# Pulser.net
KiCad netlist of a schematic drawn in Altium Designer
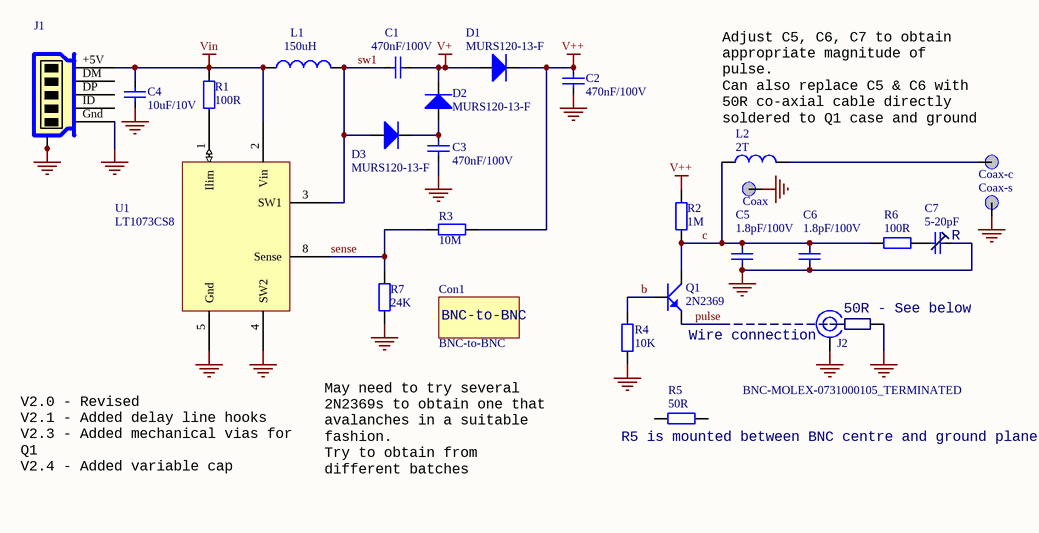
[diagram p0: Pulser.SchDoc]

(export (version "E")
  (design (tool "Eeschema 10.0.6"))
  (components
    (comp (ref "C1")
      (value "470nF/100V")
      (footprint "CCNP3216-1206")
      (description "Capacitor")
      (fields
        (field (name "MANUFACTURER") "Generic Components")
        (field (name "PUBLISHER") "Altium Hobart Technology Centre")
      )
      (libsource (lib "MyLibrary") (part "Cap"))
    )
    (comp (ref "C2")
      (value "470nF/100V")
      (footprint "CCNP3216-1206")
      (description "Capacitor")
      (fields
        (field (name "MANUFACTURER") "Generic Components")
        (field (name "PUBLISHER") "Altium Hobart Technology Centre")
      )
      (libsource (lib "MyLibrary") (part "Cap"))
    )
    (comp (ref "C3")
      (value "470nF/100V")
      (footprint "CCNP3216-1206")
      (description "Capacitor")
      (fields
        (field (name "MANUFACTURER") "Generic Components")
        (field (name "PUBLISHER") "Altium Hobart Technology Centre")
      )
      (libsource (lib "MyLibrary") (part "Cap"))
    )
    (comp (ref "C4")
      (value "10uF/10V")
      (footprint "CCNP2012-0805")
      (description "Capacitor SMT 0805")
      (fields
        (field (name "MANUFACTURER") "Generic Components")
        (field (name "PUBLISHER") "Altium Hobart Technology Centre")
      )
      (libsource (lib "MyLibrary") (part "Cap_CCNP_0805"))
    )
    (comp (ref "C5")
      (value "1.8pF/100V")
      (footprint "CCNP2012-0805")
      (description "Capacitor")
      (fields
        (field (name "MANUFACTURER") "Generic Components")
        (field (name "PUBLISHER") "Altium Hobart Technology Centre")
      )
      (libsource (lib "MyLibrary") (part "Cap"))
    )
    (comp (ref "C6")
      (value "1.8pF/100V")
      (footprint "CCNP2012-0805")
      (description "Capacitor")
      (fields
        (field (name "MANUFACTURER") "Generic Components")
        (field (name "PUBLISHER") "Altium Hobart Technology Centre")
      )
      (libsource (lib "MyLibrary") (part "Cap"))
    )
    (comp (ref "C7")
      (value "5-20pF")
      (footprint "MyPcbLib:CAP_TRIM_SMT_TZC3")
      (description "Trimmer Capacitor muRata TZC3 series")
      (fields
        (field (name "MANUFACTURER") "Generic Components")
        (field (name "PUBLISHER") "Altium Hobart Technology Centre")
      )
      (libsource (lib "MySchLib") (part "Cap_Trimmer_TZC3"))
    )
    (comp (ref "Coax") (value "PAD") (footprint "Pad") (libsource (lib "MyLibrary") (part "PAD")))
    (comp (ref "Coax-c") (value "PAD") (footprint "Pad") (libsource (lib "MyLibrary") (part "PAD")))
    (comp (ref "Coax-s") (value "PAD") (footprint "Pad") (libsource (lib "MyLibrary") (part "PAD")))
    (comp (ref "Con1")
      (value "BNC-to-BNC")
      (footprint "BNC-to-BNC")
      (libsource (lib "MySchLib") (part "BNC-to-BNC"))
    )
    (comp (ref "D1")
      (value "MURS120-13-F")
      (footprint "SMB_Diode")
      (description "Fast / Ultrafast Diode, 200 V, 1 A")
      (fields
        (field (name "MANUFACTURER") "Generic Components")
        (field (name "PUBLISHER") "Altium Hobart Technology Centre")
      )
      (libsource (lib "MySchLib") (part "MURS120-13-F"))
    )
    (comp (ref "D2")
      (value "MURS120-13-F")
      (footprint "SMB_Diode")
      (description "Fast / Ultrafast Diode, 200 V, 1 A")
      (fields
        (field (name "MANUFACTURER") "Generic Components")
        (field (name "PUBLISHER") "Altium Hobart Technology Centre")
      )
      (libsource (lib "MySchLib") (part "MURS120-13-F"))
    )
    (comp (ref "D3")
      (value "MURS120-13-F")
      (footprint "SMB_Diode")
      (description "Fast / Ultrafast Diode, 200 V, 1 A")
      (fields
        (field (name "MANUFACTURER") "Generic Components")
        (field (name "PUBLISHER") "Altium Hobart Technology Centre")
      )
      (libsource (lib "MySchLib") (part "MURS120-13-F"))
    )
    (comp (ref "J1")
      (value "USB_MICRO_B_CONNECTOR")
      (footprint "MOLEX - 47346-0001")
      (description "USB Micro-B Connector")
      (libsource (lib "MyLibrary") (part "USB_MICRO_B_CONNECTOR"))
    )
    (comp (ref "J2")
      (value "BNC-MOLEX-0731000105_TERMINATED")
      (footprint "BNC_RA CON - Molex - Resistor")
      (description "BNC Connector")
      (libsource (lib "MyLibrary") (part "BNC-MOLEX-0731000105_TERMINATED"))
    )
    (comp (ref "L1")
      (value "150uH")
      (footprint "INDUCTOR_SMT")
      (description "Inductor - SMT 3mm")
      (libsource (lib "MySchLib") (part "INDUCTOR-SMT"))
    )
    (comp (ref "L2")
      (value "2T")
      (footprint "CL2012-0805")
      (description "Resistor")
      (fields
        (field (name "MANUFACTURER") "Generic Components")
        (field (name "PUBLISHER") "Altium Hobart Technology Centre")
      )
      (libsource (lib "MyLibrary") (part "Ind_CL0805"))
    )
    (comp (ref "Q1")
      (value "2N2369")
      (footprint "TO-18-flush")
      (description "High Speed Switching Transistor")
      (libsource (lib "MySchLib") (part "2N2369"))
    )
    (comp (ref "R1")
      (value "100R")
      (footprint "CR2012-0805")
      (description "Resistor")
      (fields
        (field (name "MANUFACTURER") "Generic Components")
        (field (name "PUBLISHER") "Altium Hobart Technology Centre")
      )
      (libsource (lib "") (part "Res_1"))
    )
    (comp (ref "R2")
      (value "1M")
      (footprint "CR2012-0805")
      (description "Resistor")
      (fields
        (field (name "MANUFACTURER") "Generic Components")
        (field (name "PUBLISHER") "Altium Hobart Technology Centre")
      )
      (libsource (lib "") (part "Res_1"))
    )
    (comp (ref "R3")
      (value "10M")
      (footprint "CR2012-0805")
      (description "Resistor")
      (fields
        (field (name "MANUFACTURER") "Generic Components")
        (field (name "PUBLISHER") "Altium Hobart Technology Centre")
      )
      (libsource (lib "") (part "Res_2"))
    )
    (comp (ref "R4")
      (value "10K")
      (footprint "CR2012-0805")
      (description "Resistor")
      (fields
        (field (name "MANUFACTURER") "Generic Components")
        (field (name "PUBLISHER") "Altium Hobart Technology Centre")
      )
      (libsource (lib "MyLibrary") (part "Res"))
    )
    (comp (ref "R5")
      (value "50R")
      (footprint "CR3216-1206")
      (description "Resistor")
      (fields
        (field (name "MANUFACTURER") "Generic Components")
        (field (name "PUBLISHER") "Altium Hobart Technology Centre")
      )
      (libsource (lib "") (part "Res_3"))
    )
    (comp (ref "R6")
      (value "100R")
      (footprint "CR2012-0805")
      (description "Resistor")
      (fields
        (field (name "MANUFACTURER") "Generic Components")
        (field (name "PUBLISHER") "Altium Hobart Technology Centre")
      )
      (libsource (lib "MyLibrary") (part "Res"))
    )
    (comp (ref "R7")
      (value "24K")
      (footprint "CR2012-0805")
      (description "Resistor")
      (fields
        (field (name "MANUFACTURER") "Generic Components")
        (field (name "PUBLISHER") "Altium Hobart Technology Centre")
      )
      (libsource (lib "MyLibrary") (part "Res"))
    )
    (comp (ref "U1")
      (value "LT1073CS8")
      (footprint "SO-8_L")
      (description "Micropower DC/DC Converter (Adjustable, 212mV reference)")
      (libsource (lib "MySchLib") (part "LT1073CS8"))
    )
  )
  (nets
    (net (code "1") (name "/b") (class "Default")
      (node (ref "Q1") (pin "B") (pinfunction "B_B") (pintype "passive"))
      (node (ref "R4") (pin "2") (pinfunction "2_2") (pintype "passive"))
    )
    (net (code "2") (name "/c") (class "Default")
      (node (ref "C5") (pin "2") (pinfunction "2_2") (pintype "passive"))
      (node (ref "C6") (pin "2") (pinfunction "2_2") (pintype "passive"))
      (node (ref "L2") (pin "1") (pinfunction "1_1") (pintype "passive"))
      (node (ref "Q1") (pin "C") (pinfunction "C_C") (pintype "passive"))
      (node (ref "R2") (pin "2") (pinfunction "2_2") (pintype "passive"))
      (node (ref "R6") (pin "1") (pinfunction "1_1") (pintype "passive"))
    )
    (net (code "3") (name "/pulse") (class "Default")
      (node (ref "Q1") (pin "E") (pinfunction "E_E") (pintype "passive"))
    )
    (net (code "4") (name "/sense") (class "Default")
      (node (ref "R3") (pin "1") (pinfunction "1_1") (pintype "passive"))
      (node (ref "R7") (pin "2") (pinfunction "2_2") (pintype "passive"))
      (node (ref "U1") (pin "8") (pinfunction "Sense_8") (pintype "passive"))
    )
    (net (code "5") (name "/sw1") (class "Default")
      (node (ref "C1") (pin "1") (pinfunction "1_1") (pintype "passive"))
      (node (ref "D3") (pin "A") (pinfunction "A_A") (pintype "passive"))
      (node (ref "L1") (pin "2") (pinfunction "2_2") (pintype "passive"))
      (node (ref "U1") (pin "3") (pinfunction "SW1_3") (pintype "passive"))
    )
    (net (code "6") (name "GND") (class "Default")
      (node (ref "C2") (pin "2") (pinfunction "2_2") (pintype "passive"))
      (node (ref "C3") (pin "1") (pinfunction "1_1") (pintype "passive"))
      (node (ref "C4") (pin "2") (pinfunction "2_2") (pintype "passive"))
      (node (ref "C5") (pin "1") (pinfunction "1_1") (pintype "passive"))
      (node (ref "C6") (pin "1") (pinfunction "1_1") (pintype "passive"))
      (node (ref "C7") (pin "R") (pinfunction "R_R") (pintype "passive"))
      (node (ref "Coax") (pin "1") (pintype "passive"))
      (node (ref "Coax-s") (pin "1") (pintype "passive"))
      (node (ref "J1") (pin "G") (pinfunction "USBGnd_G") (pintype "passive"))
      (node (ref "J1") (pin "S1") (pinfunction "USBShd_S1") (pintype "passive"))
      (node (ref "J1") (pin "S2") (pinfunction "USBShd_S2") (pintype "passive"))
      (node (ref "J1") (pin "S3") (pinfunction "USBShd_S3") (pintype "passive"))
      (node (ref "J1") (pin "S4") (pinfunction "USBShd_S4") (pintype "passive"))
      (node (ref "J1") (pin "S5") (pinfunction "USBShd_S5") (pintype "passive"))
      (node (ref "J1") (pin "S6") (pinfunction "USBShd_S6") (pintype "passive"))
      (node (ref "J2") (pin "1") (pinfunction "1_1") (pintype "passive"))
      (node (ref "J2") (pin "2") (pinfunction "2_2") (pintype "passive"))
      (node (ref "R4") (pin "1") (pinfunction "1_1") (pintype "passive"))
      (node (ref "R7") (pin "1") (pinfunction "1_1") (pintype "passive"))
      (node (ref "U1") (pin "4") (pinfunction "SW2_4") (pintype "passive"))
      (node (ref "U1") (pin "5") (pinfunction "Gnd_5") (pintype "power_in"))
    )
    (net (code "7") (name "Net-(C3-Pad2)") (class "Default")
      (node (ref "C3") (pin "2") (pinfunction "2_2") (pintype "passive"))
      (node (ref "D2") (pin "A") (pinfunction "A_A") (pintype "passive"))
      (node (ref "D3") (pin "K") (pinfunction "K_K") (pintype "passive"))
    )
    (net (code "8") (name "Net-(C7-PadS)") (class "Default")
      (node (ref "C7") (pin "S") (pinfunction "S_S") (pintype "passive"))
      (node (ref "R6") (pin "2") (pinfunction "2_2") (pintype "passive"))
    )
    (net (code "9") (name "Net-(Coax-c-Pad1)") (class "Default")
      (node (ref "Coax-c") (pin "1") (pintype "passive"))
      (node (ref "L2") (pin "2") (pinfunction "2_2") (pintype "passive"))
    )
    (net (code "10") (name "Net-(U1-Ilim)") (class "Default")
      (node (ref "R1") (pin "2") (pinfunction "2_2") (pintype "passive"))
      (node (ref "U1") (pin "1") (pinfunction "Ilim_1") (pintype "bidirectional"))
    )
    (net (code "11") (name "V+") (class "Default")
      (node (ref "C1") (pin "2") (pinfunction "2_2") (pintype "passive"))
      (node (ref "D1") (pin "A") (pinfunction "A_A") (pintype "passive"))
      (node (ref "D2") (pin "K") (pinfunction "K_K") (pintype "passive"))
    )
    (net (code "12") (name "V++") (class "Default")
      (node (ref "C2") (pin "1") (pinfunction "1_1") (pintype "passive"))
      (node (ref "D1") (pin "K") (pinfunction "K_K") (pintype "passive"))
      (node (ref "R2") (pin "1") (pinfunction "1_1") (pintype "passive"))
      (node (ref "R3") (pin "2") (pinfunction "2_2") (pintype "passive"))
    )
    (net (code "13") (name "Vin") (class "Default")
      (node (ref "C4") (pin "1") (pinfunction "1_1") (pintype "passive"))
      (node (ref "J1") (pin "VBUS") (pinfunction "USB+5v_VBUS") (pintype "power_in"))
      (node (ref "L1") (pin "1") (pinfunction "1_1") (pintype "passive"))
      (node (ref "R1") (pin "1") (pinfunction "1_1") (pintype "passive"))
      (node (ref "U1") (pin "2") (pinfunction "Vin_2") (pintype "power_in"))
    )
    (net (code "14") (name "unconnected-(J1-USBDM-PadD-)") (class "Default")
      (node (ref "J1") (pin "D-") (pinfunction "USBDM_D-") (pintype "passive"))
    )
    (net (code "15") (name "unconnected-(J1-USBDP-PadD+)") (class "Default")
      (node (ref "J1") (pin "D+") (pinfunction "USBDP_D+") (pintype "passive"))
    )
    (net (code "16") (name "unconnected-(J1-USB_ID-PadID)") (class "Default")
      (node (ref "J1") (pin "ID") (pinfunction "USB_ID_ID") (pintype "passive"))
    )
    (net (code "17") (name "unconnected-(R5-Pad1)") (class "Default")
      (node (ref "R5") (pin "1") (pinfunction "1_1") (pintype "passive"))
    )
    (net (code "18") (name "unconnected-(R5-Pad2)") (class "Default")
      (node (ref "R5") (pin "2") (pinfunction "2_2") (pintype "passive"))
    )
  )
)
